# 3_3Reg.net
KiCad netlist of a schematic drawn in Altium Designer
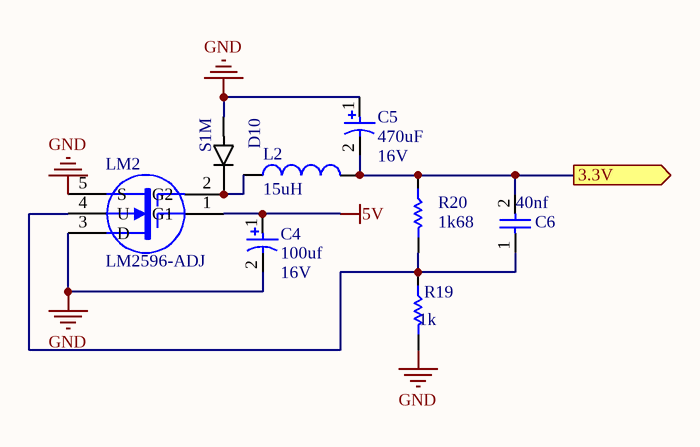
[diagram p0: 3_3Reg.SchDoc]

(export (version "E")
  (design (tool "Eeschema 10.0.6"))
  (components
    (comp (ref "C4")
      (value "100uf")
      (footprint "RB5-10.5")
      (fields (field (name "ALTIUM_UNNAMED_8") "16V"))
      (libsource (lib "3D LIB") (part "CAP"))
    )
    (comp (ref "C5")
      (value "470uF")
      (footprint "RB5-10.5")
      (fields (field (name "ALTIUM_UNNAMED_8") "16V"))
      (libsource (lib "3D LIB") (part "CAP"))
    )
    (comp (ref "C6") (value "40nf") (footprint "6-0805_L") (libsource (lib "3D LIB") (part "CAP NON")))
    (comp (ref "D10")
      (value "S1M")
      (footprint "*DIOM5227X270N_S1M(Primary)")
      (description "S1 Series 1000 V 1 A 1 uA Surface Mount General Purpose Rectifier - DO-214AC")
      (fields (field (name "MF") "ON Semiconductor"))
      (libsource (lib "S1M") (part "S1M"))
    )
    (comp (ref "L2")
      (value "15uH")
      (footprint "IND_SMD-13.0mm")
      (description "Inductor")
      (libsource (lib "3D LIB") (part "Inductor"))
    )
    (comp (ref "LM2")
      (value "LM2596-ADJ")
      (footprint "T05A")
      (description "Two-Gate, N-Channel MOSFET, Externally Terminated Substrate")
      (fields (field (name "PUBLISHER") "Altium Limited"))
      (libsource (lib "Miscellaneous Devices") (part "MOSFET-N3"))
    )
    (comp (ref "R19") (value "1k") (footprint "6-0805_L") (libsource (lib "3D LIB") (part "RESISTOR")))
    (comp (ref "R20") (value "1k68") (footprint "6-0805_L") (libsource (lib "3D LIB") (part "RESISTOR")))
  )
  (nets
    (net (code "1") (name "/3.3V") (class "Default")
      (node (ref "C5") (pin "2") (pinfunction "2_2") (pintype "passive"))
      (node (ref "C6") (pin "2") (pinfunction "2_2") (pintype "passive"))
      (node (ref "L2") (pin "2") (pinfunction "2_2") (pintype "passive"))
      (node (ref "R20") (pin "1") (pinfunction "1_1") (pintype "passive"))
    )
    (net (code "2") (name "5V") (class "Default")
      (node (ref "C4") (pin "1") (pinfunction "1_1") (pintype "passive"))
      (node (ref "LM2") (pin "1") (pinfunction "G1_1") (pintype "passive"))
    )
    (net (code "3") (name "GND") (class "Default")
      (node (ref "C4") (pin "2") (pinfunction "2_2") (pintype "passive"))
      (node (ref "C5") (pin "1") (pinfunction "1_1") (pintype "passive"))
      (node (ref "D10") (pin "A") (pinfunction "A_A") (pintype "passive"))
      (node (ref "LM2") (pin "3") (pinfunction "D_3") (pintype "passive"))
      (node (ref "LM2") (pin "5") (pinfunction "S_5") (pintype "passive"))
      (node (ref "R19") (pin "2") (pinfunction "2_2") (pintype "passive"))
    )
    (net (code "4") (name "Net-(D10-K)") (class "Default")
      (node (ref "D10") (pin "C") (pinfunction "K_C") (pintype "passive"))
      (node (ref "L2") (pin "1") (pinfunction "1_1") (pintype "passive"))
      (node (ref "LM2") (pin "2") (pinfunction "G2_2") (pintype "passive"))
    )
    (net (code "5") (name "Net-(LM2-U)") (class "Default")
      (node (ref "C6") (pin "1") (pinfunction "1_1") (pintype "passive"))
      (node (ref "LM2") (pin "4") (pinfunction "U_4") (pintype "passive"))
      (node (ref "R19") (pin "1") (pinfunction "1_1") (pintype "passive"))
      (node (ref "R20") (pin "2") (pinfunction "2_2") (pintype "passive"))
    )
  )
)
